# 04A-020.net
KiCad netlist of a schematic drawn in EAGLE
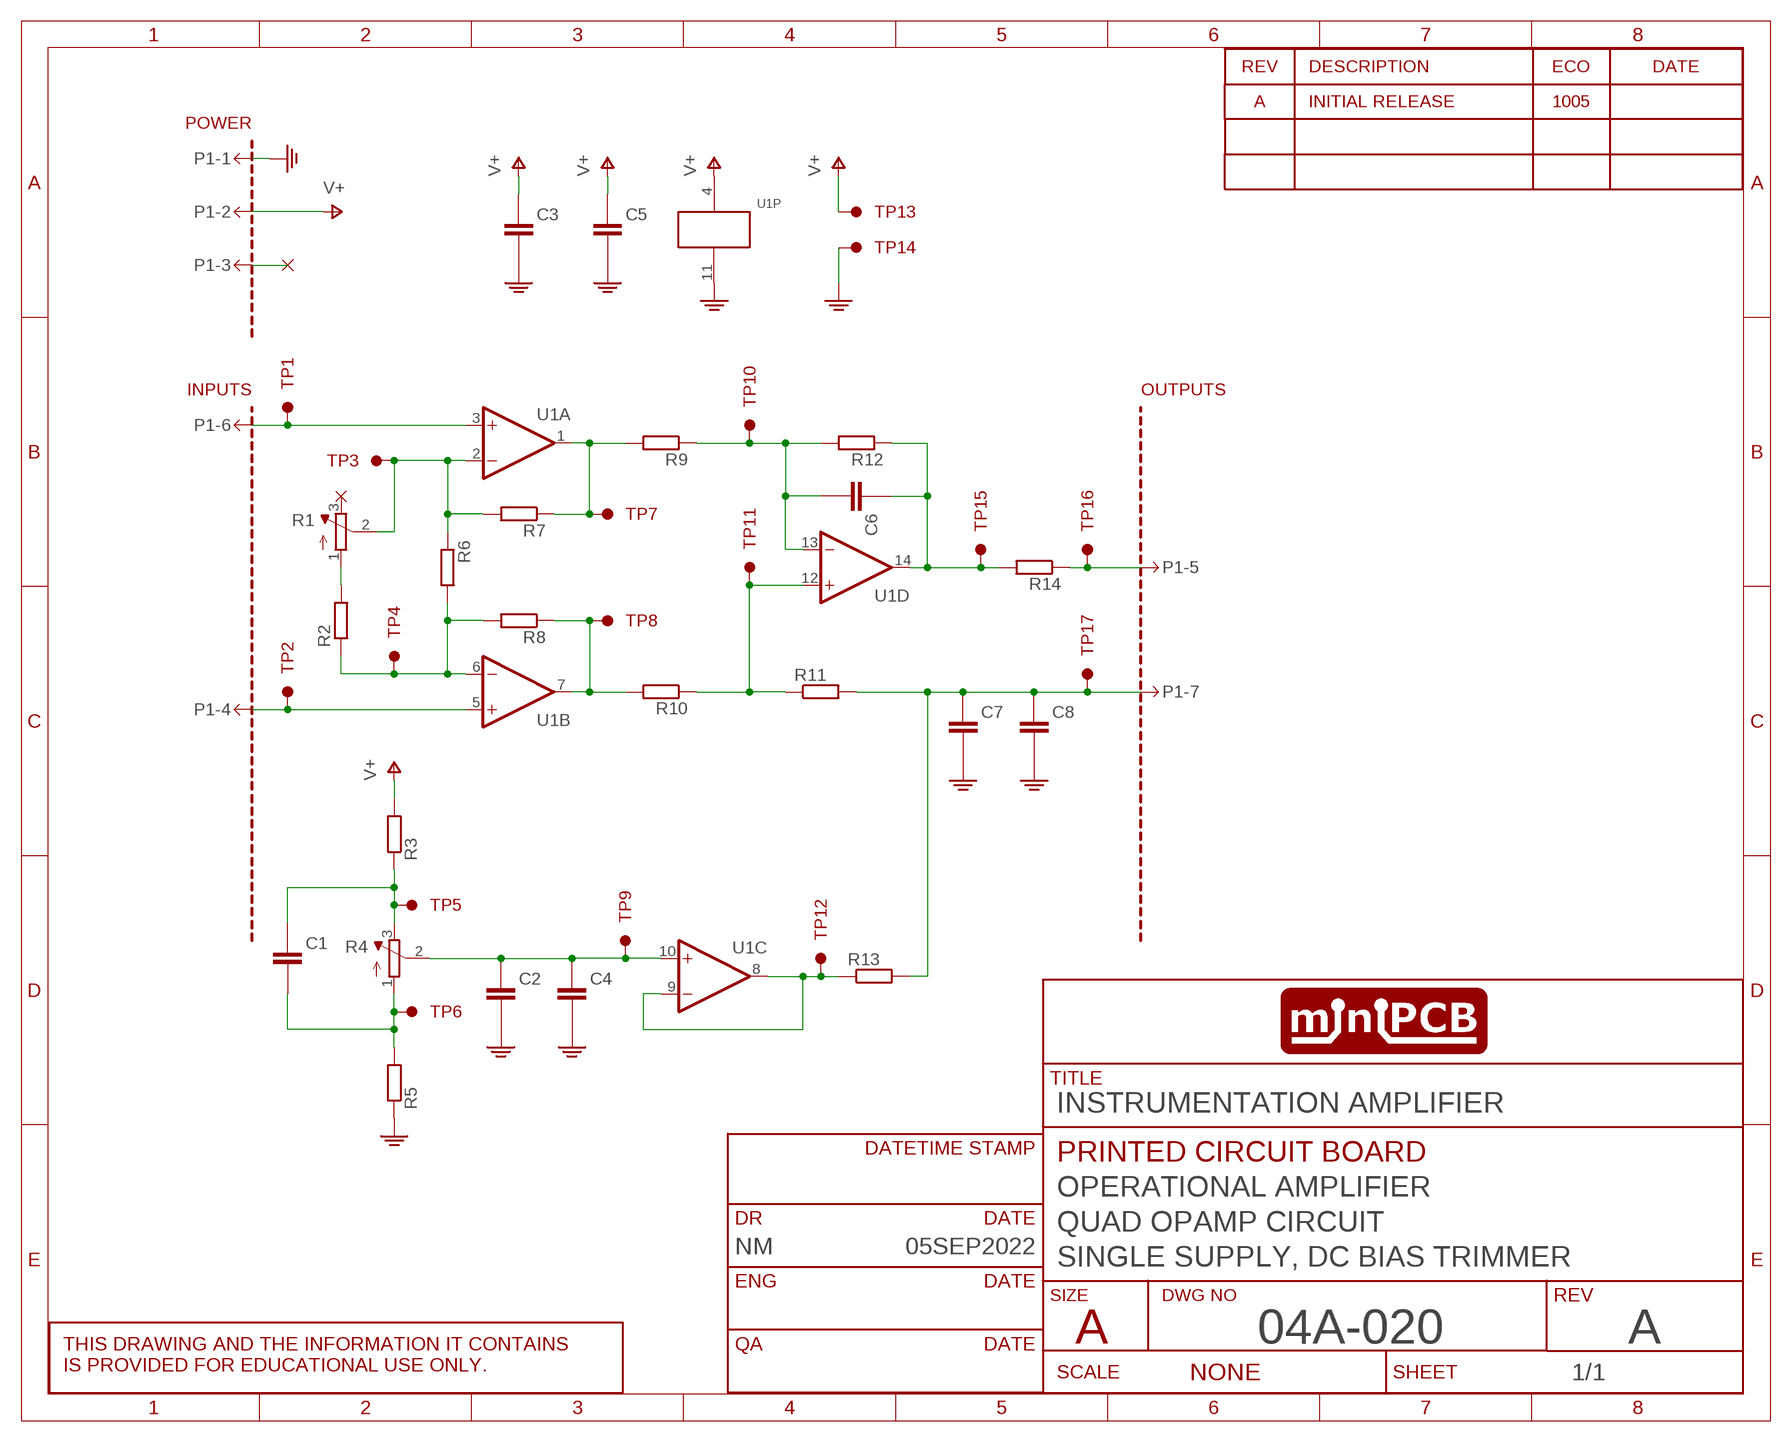
[diagram p0: schematic, sheet 1]

(export (version "E")
  (design (tool "Eeschema 10.0.6"))
  (components
    (comp (ref "C1")
      (value "CAPACITORTHD")
      (footprint "eagle-import:C050-024X044")
      (libsource (lib "eagle-import") (part "CAPACITORTHD"))
    )
    (comp (ref "C2")
      (value "CAPACITORTHD")
      (footprint "eagle-import:C050-024X044")
      (libsource (lib "eagle-import") (part "CAPACITORTHD"))
    )
    (comp (ref "C3")
      (value "CAPACITORTHD")
      (footprint "eagle-import:C050-024X044")
      (libsource (lib "eagle-import") (part "CAPACITORTHD"))
    )
    (comp (ref "C4")
      (value "CAPACITORTHD")
      (footprint "eagle-import:C050-024X044")
      (libsource (lib "eagle-import") (part "CAPACITORTHD"))
    )
    (comp (ref "C5")
      (value "CAPACITORTHD")
      (footprint "eagle-import:C050-024X044")
      (libsource (lib "eagle-import") (part "CAPACITORTHD"))
    )
    (comp (ref "C6")
      (value "CAPACITORTHD")
      (footprint "eagle-import:C050-024X044")
      (libsource (lib "eagle-import") (part "CAPACITORTHD"))
    )
    (comp (ref "C7")
      (value "CAPACITORTHD")
      (footprint "eagle-import:C050-024X044")
      (libsource (lib "eagle-import") (part "CAPACITORTHD"))
    )
    (comp (ref "C8")
      (value "CAPACITORTHD")
      (footprint "eagle-import:C050-024X044")
      (libsource (lib "eagle-import") (part "CAPACITORTHD"))
    )
    (comp (ref "P1-")
      (value "MINIPCB_7P50X100")
      (footprint "eagle-import:MINIPCB_7P_50X100")
      (fields (field (name "PART_NUMBER") "X04A-020-A"))
      (libsource (lib "eagle-import") (part "MINIPCB_7P50X100"))
    )
    (comp (ref "R1")
      (value "TRIMPOT0.100THD")
      (footprint "eagle-import:TRIM_0100")
      (libsource (lib "eagle-import") (part "TRIMPOT0.100THD"))
    )
    (comp (ref "R2")
      (value "RESISTOR10MM")
      (footprint "eagle-import:0207_10")
      (libsource (lib "eagle-import") (part "RESISTOR10MM"))
    )
    (comp (ref "R3")
      (value "RESISTOR10MM")
      (footprint "eagle-import:0207_10")
      (libsource (lib "eagle-import") (part "RESISTOR10MM"))
    )
    (comp (ref "R4")
      (value "TRIMPOT0.100THD")
      (footprint "eagle-import:TRIM_0100")
      (libsource (lib "eagle-import") (part "TRIMPOT0.100THD"))
    )
    (comp (ref "R5")
      (value "RESISTOR10MM")
      (footprint "eagle-import:0207_10")
      (libsource (lib "eagle-import") (part "RESISTOR10MM"))
    )
    (comp (ref "R6")
      (value "RESISTOR10MM")
      (footprint "eagle-import:0207_10")
      (libsource (lib "eagle-import") (part "RESISTOR10MM"))
    )
    (comp (ref "R7")
      (value "RESISTOR10MM")
      (footprint "eagle-import:0207_10")
      (libsource (lib "eagle-import") (part "RESISTOR10MM"))
    )
    (comp (ref "R8")
      (value "RESISTOR10MM")
      (footprint "eagle-import:0207_10")
      (libsource (lib "eagle-import") (part "RESISTOR10MM"))
    )
    (comp (ref "R9")
      (value "RESISTOR10MM")
      (footprint "eagle-import:0207_10")
      (libsource (lib "eagle-import") (part "RESISTOR10MM"))
    )
    (comp (ref "R10")
      (value "RESISTOR10MM")
      (footprint "eagle-import:0207_10")
      (libsource (lib "eagle-import") (part "RESISTOR10MM"))
    )
    (comp (ref "R11")
      (value "RESISTOR10MM")
      (footprint "eagle-import:0207_10")
      (libsource (lib "eagle-import") (part "RESISTOR10MM"))
    )
    (comp (ref "R12")
      (value "RESISTOR10MM")
      (footprint "eagle-import:0207_10")
      (libsource (lib "eagle-import") (part "RESISTOR10MM"))
    )
    (comp (ref "R13")
      (value "RESISTOR10MM")
      (footprint "eagle-import:0207_10")
      (libsource (lib "eagle-import") (part "RESISTOR10MM"))
    )
    (comp (ref "R14")
      (value "RESISTOR10MM")
      (footprint "eagle-import:0207_10")
      (libsource (lib "eagle-import") (part "RESISTOR10MM"))
    )
    (comp (ref "TP1")
      (value "TESTPOINTKE5000-SMTEXT")
      (footprint "eagle-import:PINS_1_TESTPOINT_KE5000_NOTEXT")
      (libsource (lib "eagle-import") (part "TESTPOINTKE5000-SMTEXT"))
    )
    (comp (ref "TP2")
      (value "TESTPOINTKE5000-SMTEXT")
      (footprint "eagle-import:PINS_1_TESTPOINT_KE5000_NOTEXT")
      (libsource (lib "eagle-import") (part "TESTPOINTKE5000-SMTEXT"))
    )
    (comp (ref "TP3")
      (value "TESTPOINTKE5000-SMTEXT")
      (footprint "eagle-import:PINS_1_TESTPOINT_KE5000_NOTEXT")
      (libsource (lib "eagle-import") (part "TESTPOINTKE5000-SMTEXT"))
    )
    (comp (ref "TP4")
      (value "TESTPOINTKE5000-SMTEXT")
      (footprint "eagle-import:PINS_1_TESTPOINT_KE5000_NOTEXT")
      (libsource (lib "eagle-import") (part "TESTPOINTKE5000-SMTEXT"))
    )
    (comp (ref "TP5")
      (value "TESTPOINTKE5000-SMTEXT")
      (footprint "eagle-import:PINS_1_TESTPOINT_KE5000_NOTEXT")
      (libsource (lib "eagle-import") (part "TESTPOINTKE5000-SMTEXT"))
    )
    (comp (ref "TP6")
      (value "TESTPOINTKE5000-SMTEXT")
      (footprint "eagle-import:PINS_1_TESTPOINT_KE5000_NOTEXT")
      (libsource (lib "eagle-import") (part "TESTPOINTKE5000-SMTEXT"))
    )
    (comp (ref "TP7")
      (value "TESTPOINTKE5000-SMTEXT")
      (footprint "eagle-import:PINS_1_TESTPOINT_KE5000_NOTEXT")
      (libsource (lib "eagle-import") (part "TESTPOINTKE5000-SMTEXT"))
    )
    (comp (ref "TP8")
      (value "TESTPOINTKE5000-SMTEXT")
      (footprint "eagle-import:PINS_1_TESTPOINT_KE5000_NOTEXT")
      (libsource (lib "eagle-import") (part "TESTPOINTKE5000-SMTEXT"))
    )
    (comp (ref "TP9")
      (value "TESTPOINTKE5000-SMTEXT")
      (footprint "eagle-import:PINS_1_TESTPOINT_KE5000_NOTEXT")
      (libsource (lib "eagle-import") (part "TESTPOINTKE5000-SMTEXT"))
    )
    (comp (ref "TP10")
      (value "TESTPOINTKE5000-SMTEXT")
      (footprint "eagle-import:PINS_1_TESTPOINT_KE5000_NOTEXT")
      (libsource (lib "eagle-import") (part "TESTPOINTKE5000-SMTEXT"))
    )
    (comp (ref "TP11")
      (value "TESTPOINTKE5000-SMTEXT")
      (footprint "eagle-import:PINS_1_TESTPOINT_KE5000_NOTEXT")
      (libsource (lib "eagle-import") (part "TESTPOINTKE5000-SMTEXT"))
    )
    (comp (ref "TP12")
      (value "TESTPOINTKE5000-SMTEXT")
      (footprint "eagle-import:PINS_1_TESTPOINT_KE5000_NOTEXT")
      (libsource (lib "eagle-import") (part "TESTPOINTKE5000-SMTEXT"))
    )
    (comp (ref "TP13")
      (value "TESTPOINTKE5000-SMTEXT")
      (footprint "eagle-import:PINS_1_TESTPOINT_KE5000_NOTEXT")
      (libsource (lib "eagle-import") (part "TESTPOINTKE5000-SMTEXT"))
    )
    (comp (ref "TP14")
      (value "TESTPOINTKE5000-SMTEXT")
      (footprint "eagle-import:PINS_1_TESTPOINT_KE5000_NOTEXT")
      (libsource (lib "eagle-import") (part "TESTPOINTKE5000-SMTEXT"))
    )
    (comp (ref "TP15")
      (value "TESTPOINTKE5000-SMTEXT")
      (footprint "eagle-import:PINS_1_TESTPOINT_KE5000_NOTEXT")
      (libsource (lib "eagle-import") (part "TESTPOINTKE5000-SMTEXT"))
    )
    (comp (ref "TP16")
      (value "TESTPOINTKE5000-SMTEXT")
      (footprint "eagle-import:PINS_1_TESTPOINT_KE5000_NOTEXT")
      (libsource (lib "eagle-import") (part "TESTPOINTKE5000-SMTEXT"))
    )
    (comp (ref "TP17")
      (value "TESTPOINTKE5000-SMTEXT")
      (footprint "eagle-import:PINS_1_TESTPOINT_KE5000_NOTEXT")
      (libsource (lib "eagle-import") (part "TESTPOINTKE5000-SMTEXT"))
    )
    (comp (ref "U1")
      (value "OPAMP_QUADTHD")
      (footprint "eagle-import:DIL14")
      (libsource (lib "eagle-import") (part "OPAMP_QUADTHD"))
    )
  )
  (nets
    (net (code "1") (name "GND") (class "Default")
      (node (ref "C2") (pin "2") (pinfunction "-_2") (pintype "passive"))
      (node (ref "C3") (pin "2") (pinfunction "-_2") (pintype "passive"))
      (node (ref "C4") (pin "2") (pinfunction "-_2") (pintype "passive"))
      (node (ref "C5") (pin "2") (pinfunction "-_2") (pintype "passive"))
      (node (ref "C7") (pin "2") (pinfunction "-_2") (pintype "passive"))
      (node (ref "C8") (pin "2") (pinfunction "-_2") (pintype "passive"))
      (node (ref "P1-") (pin "1") (pinfunction "1_1") (pintype "bidirectional"))
      (node (ref "R5") (pin "1") (pinfunction "1_1") (pintype "passive"))
      (node (ref "TP14") (pin "1") (pinfunction "1_1") (pintype "bidirectional"))
      (node (ref "U1") (pin "11") (pinfunction "V-_11") (pintype "power_in"))
    )
    (net (code "2") (name "Net-(C1-+)") (class "Default")
      (node (ref "C1") (pin "1") (pinfunction "+_1") (pintype "passive"))
      (node (ref "R3") (pin "1") (pinfunction "1_1") (pintype "passive"))
      (node (ref "R4") (pin "3") (pinfunction "E_3") (pintype "passive"))
      (node (ref "TP5") (pin "1") (pinfunction "1_1") (pintype "bidirectional"))
    )
    (net (code "3") (name "Net-(C1--)") (class "Default")
      (node (ref "C1") (pin "2") (pinfunction "-_2") (pintype "passive"))
      (node (ref "R4") (pin "1") (pinfunction "A_1") (pintype "passive"))
      (node (ref "R5") (pin "2") (pinfunction "2_2") (pintype "passive"))
      (node (ref "TP6") (pin "1") (pinfunction "1_1") (pintype "bidirectional"))
    )
    (net (code "4") (name "Net-(C2-+)") (class "Default")
      (node (ref "C2") (pin "1") (pinfunction "+_1") (pintype "passive"))
      (node (ref "C4") (pin "1") (pinfunction "+_1") (pintype "passive"))
      (node (ref "R4") (pin "2") (pinfunction "S_2") (pintype "passive"))
      (node (ref "TP9") (pin "1") (pinfunction "1_1") (pintype "bidirectional"))
      (node (ref "U1") (pin "10") (pinfunction "+IN_10") (pintype "input"))
    )
    (net (code "5") (name "Net-(C6-+)") (class "Default")
      (node (ref "C6") (pin "1") (pinfunction "+_1") (pintype "passive"))
      (node (ref "R12") (pin "1") (pinfunction "1_1") (pintype "passive"))
      (node (ref "R14") (pin "2") (pinfunction "2_2") (pintype "passive"))
      (node (ref "TP15") (pin "1") (pinfunction "1_1") (pintype "bidirectional"))
      (node (ref "U1") (pin "14") (pinfunction "OUT_14") (pintype "output"))
    )
    (net (code "6") (name "Net-(C6--)") (class "Default")
      (node (ref "C6") (pin "2") (pinfunction "-_2") (pintype "passive"))
      (node (ref "R12") (pin "2") (pinfunction "2_2") (pintype "passive"))
      (node (ref "R9") (pin "1") (pinfunction "1_1") (pintype "passive"))
      (node (ref "TP10") (pin "1") (pinfunction "1_1") (pintype "bidirectional"))
      (node (ref "U1") (pin "13") (pinfunction "-IN_13") (pintype "input"))
    )
    (net (code "7") (name "Net-(C7-+)") (class "Default")
      (node (ref "C7") (pin "1") (pinfunction "+_1") (pintype "passive"))
      (node (ref "C8") (pin "1") (pinfunction "+_1") (pintype "passive"))
      (node (ref "P1-") (pin "7") (pinfunction "1_7") (pintype "bidirectional"))
      (node (ref "R11") (pin "2") (pinfunction "2_2") (pintype "passive"))
      (node (ref "R13") (pin "2") (pinfunction "2_2") (pintype "passive"))
      (node (ref "TP17") (pin "1") (pinfunction "1_1") (pintype "bidirectional"))
    )
    (net (code "8") (name "Net-(P1-D-1)") (class "Default")
      (node (ref "P1-") (pin "4") (pinfunction "1_4") (pintype "bidirectional"))
      (node (ref "TP2") (pin "1") (pinfunction "1_1") (pintype "bidirectional"))
      (node (ref "U1") (pin "5") (pinfunction "+IN_5") (pintype "input"))
    )
    (net (code "9") (name "Net-(P1-E-1)") (class "Default")
      (node (ref "P1-") (pin "5") (pinfunction "1_5") (pintype "bidirectional"))
      (node (ref "R14") (pin "1") (pinfunction "1_1") (pintype "passive"))
      (node (ref "TP16") (pin "1") (pinfunction "1_1") (pintype "bidirectional"))
    )
    (net (code "10") (name "Net-(P1-F-1)") (class "Default")
      (node (ref "P1-") (pin "6") (pinfunction "1_6") (pintype "bidirectional"))
      (node (ref "TP1") (pin "1") (pinfunction "1_1") (pintype "bidirectional"))
      (node (ref "U1") (pin "3") (pinfunction "+IN_3") (pintype "input"))
    )
    (net (code "11") (name "Net-(R1-A)") (class "Default")
      (node (ref "R1") (pin "1") (pinfunction "A_1") (pintype "passive"))
      (node (ref "R2") (pin "2") (pinfunction "2_2") (pintype "passive"))
    )
    (net (code "12") (name "Net-(R1-S)") (class "Default")
      (node (ref "R1") (pin "2") (pinfunction "S_2") (pintype "passive"))
      (node (ref "R6") (pin "1") (pinfunction "1_1") (pintype "passive"))
      (node (ref "R7") (pin "2") (pinfunction "2_2") (pintype "passive"))
      (node (ref "TP3") (pin "1") (pinfunction "1_1") (pintype "bidirectional"))
      (node (ref "U1") (pin "2") (pinfunction "-IN_2") (pintype "input"))
    )
    (net (code "13") (name "Net-(U1A-OUT)") (class "Default")
      (node (ref "R7") (pin "1") (pinfunction "1_1") (pintype "passive"))
      (node (ref "R9") (pin "2") (pinfunction "2_2") (pintype "passive"))
      (node (ref "TP7") (pin "1") (pinfunction "1_1") (pintype "bidirectional"))
      (node (ref "U1") (pin "1") (pinfunction "OUT_1") (pintype "output"))
    )
    (net (code "14") (name "Net-(U1B--IN)") (class "Default")
      (node (ref "R2") (pin "1") (pinfunction "1_1") (pintype "passive"))
      (node (ref "R6") (pin "2") (pinfunction "2_2") (pintype "passive"))
      (node (ref "R8") (pin "2") (pinfunction "2_2") (pintype "passive"))
      (node (ref "TP4") (pin "1") (pinfunction "1_1") (pintype "bidirectional"))
      (node (ref "U1") (pin "6") (pinfunction "-IN_6") (pintype "input"))
    )
    (net (code "15") (name "Net-(U1B-OUT)") (class "Default")
      (node (ref "R10") (pin "2") (pinfunction "2_2") (pintype "passive"))
      (node (ref "R8") (pin "1") (pinfunction "1_1") (pintype "passive"))
      (node (ref "TP8") (pin "1") (pinfunction "1_1") (pintype "bidirectional"))
      (node (ref "U1") (pin "7") (pinfunction "OUT_7") (pintype "output"))
    )
    (net (code "16") (name "Net-(U1C--IN)") (class "Default")
      (node (ref "R13") (pin "1") (pinfunction "1_1") (pintype "passive"))
      (node (ref "TP12") (pin "1") (pinfunction "1_1") (pintype "bidirectional"))
      (node (ref "U1") (pin "8") (pinfunction "OUT_8") (pintype "output"))
      (node (ref "U1") (pin "9") (pinfunction "-IN_9") (pintype "input"))
    )
    (net (code "17") (name "Net-(U1D-+IN)") (class "Default")
      (node (ref "R10") (pin "1") (pinfunction "1_1") (pintype "passive"))
      (node (ref "R11") (pin "1") (pinfunction "1_1") (pintype "passive"))
      (node (ref "TP11") (pin "1") (pinfunction "1_1") (pintype "bidirectional"))
      (node (ref "U1") (pin "12") (pinfunction "+IN_12") (pintype "input"))
    )
    (net (code "18") (name "V+") (class "Default")
      (node (ref "C3") (pin "1") (pinfunction "+_1") (pintype "passive"))
      (node (ref "C5") (pin "1") (pinfunction "+_1") (pintype "passive"))
      (node (ref "P1-") (pin "2") (pinfunction "1_2") (pintype "bidirectional"))
      (node (ref "R3") (pin "2") (pinfunction "2_2") (pintype "passive"))
      (node (ref "TP13") (pin "1") (pinfunction "1_1") (pintype "bidirectional"))
      (node (ref "U1") (pin "4") (pinfunction "V+_4") (pintype "power_in"))
    )
    (net (code "19") (name "unconnected-(P1-C-1-Pad3)") (class "Default")
      (node (ref "P1-") (pin "3") (pinfunction "1_3") (pintype "bidirectional"))
    )
    (net (code "20") (name "unconnected-(R1-E-Pad3)") (class "Default")
      (node (ref "R1") (pin "3") (pinfunction "E_3") (pintype "passive"))
    )
  )
)
